# 06_Gyroscope.net
KiCad netlist of a schematic drawn in Altium Designer
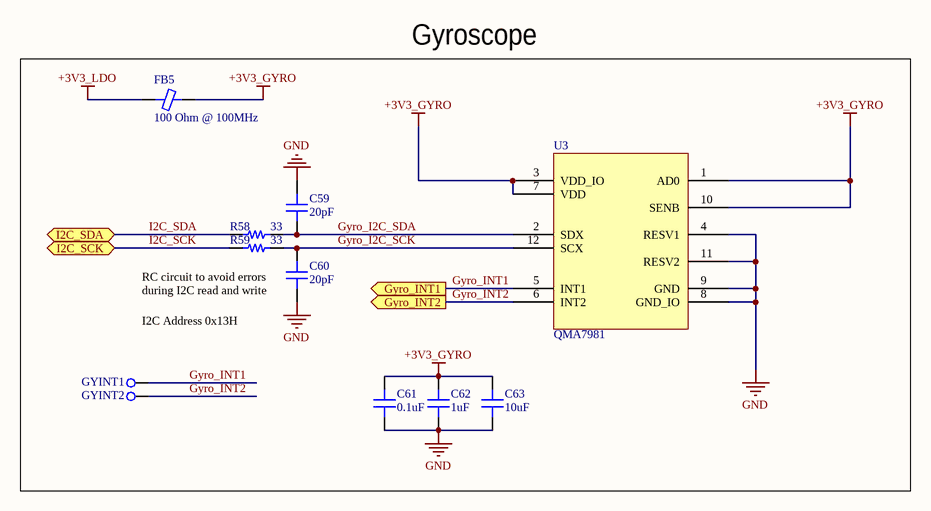
[diagram p0: [06] Gyroscope.SchDoc]

(export (version "E")
  (design (tool "Eeschema 10.0.6"))
  (components
    (comp (ref "C59")
      (value "20pF")
      (footprint "CAP 0402/1005")
      (description "CAP CER 20PF 25V NP0 0402")
      (fields
        (field (name "PART NUMBER") "GRM1555C1E200JA01D")
        (field (name "MANUFACTURER") "Murata Electronics North America")
      )
      (libsource (lib "Celestial Library Database") (part "Capacitor"))
    )
    (comp (ref "C60")
      (value "20pF")
      (footprint "CAP 0402/1005")
      (description "CAP CER 20PF 25V NP0 0402")
      (fields
        (field (name "PART NUMBER") "GRM1555C1E200JA01D")
        (field (name "MANUFACTURER") "Murata Electronics North America")
      )
      (libsource (lib "Celestial Library Database") (part "Capacitor"))
    )
    (comp (ref "C61")
      (value "0.1uF")
      (footprint "CAP 0402/1005")
      (description "CAP CER 0.1UF 10V X7R 0402")
      (fields
        (field (name "PART NUMBER") "C1005X7R1A104K050BB")
        (field (name "MANUFACTURER") "TDK Corporation")
      )
      (libsource (lib "Celestial Library Database") (part "Capacitor"))
    )
    (comp (ref "C62")
      (value "1uF")
      (footprint "CAP 0603/1608")
      (description "CAP CER 1UF 10V X7R 0603")
      (fields
        (field (name "PART NUMBER") "CGB3B1X7R1A105K055AC")
        (field (name "MANUFACTURER") "TDK Corporation")
      )
      (libsource (lib "Celestial Library Database") (part "Capacitor"))
    )
    (comp (ref "C63")
      (value "10uF")
      (footprint "CAP 0603/1608")
      (description "CAP CER 10UF 10V X5R 0603")
      (fields
        (field (name "PART NUMBER") "C1608X5R1A106M080AC")
        (field (name "MANUFACTURER") "TDK Corporation")
      )
      (libsource (lib "Celestial Library Database") (part "Capacitor"))
    )
    (comp (ref "FB5")
      (value "100 Ohm @ 100MHz")
      (footprint "FER 0603/1608")
      (description "FERRITE CHIP 100 OHM 0603")
      (fields (field (name "PART NUMBER") "BKP1608HS101-T") (field (name "MANUFACTURER") "Taiyo Yuden"))
      (libsource (lib "Celestial Library Database") (part "Ferrite Chip"))
    )
    (comp (ref "GYINT1")
      (value "RCT-0C")
      (footprint "3D FootPrint_Backup:0.5mm-TestPad")
      (description "0805 PROBE PAD")
      (fields (field (name "MANUFACTURER") "TE Connectivity AMP Connectors"))
      (libsource (lib "Celestial Library Database") (part "Test Point"))
    )
    (comp (ref "GYINT2")
      (value "RCT-0C")
      (footprint "3D FootPrint_Backup:0.5mm-TestPad")
      (description "0805 PROBE PAD")
      (fields (field (name "MANUFACTURER") "TE Connectivity AMP Connectors"))
      (libsource (lib "Celestial Library Database") (part "Test Point"))
    )
    (comp (ref "R58")
      (value "33")
      (footprint "RES 0402/1005")
      (description "RES SMD 33 OHM 5% 1/10W 0402")
      (fields
        (field (name "PART NUMBER") "ERJ-2GEJ330X")
        (field (name "MANUFACTURER") "Panasonic Electronic Components")
      )
      (libsource (lib "Celestial Library Database") (part "Resistor"))
    )
    (comp (ref "R59")
      (value "33")
      (footprint "RES 0402/1005")
      (description "RES SMD 33 OHM 5% 1/10W 0402")
      (fields
        (field (name "PART NUMBER") "ERJ-2GEJ330X")
        (field (name "MANUFACTURER") "Panasonic Electronic Components")
      )
      (libsource (lib "Celestial Library Database") (part "Resistor"))
    )
    (comp (ref "U3")
      (value "QMA7981")
      (footprint "LGA-12 2x2")
      (description "3 AXIS ACCEL 12LGA")
      (fields (field (name "MANUFACTURER") "QST"))
      (libsource (lib "Celestial Library Database") (part "QMA7981"))
    )
  )
  (nets
    (net (code "1") (name "+3V3_GYRO") (class "Default")
      (node (ref "C61") (pin "2") (pinfunction "2_2") (pintype "passive"))
      (node (ref "C62") (pin "2") (pinfunction "2_2") (pintype "passive"))
      (node (ref "C63") (pin "2") (pinfunction "2_2") (pintype "passive"))
      (node (ref "FB5") (pin "2") (pinfunction "2_2") (pintype "passive"))
      (node (ref "U3") (pin "1") (pinfunction "AD0_1") (pintype "passive"))
      (node (ref "U3") (pin "10") (pinfunction "SENB_10") (pintype "passive"))
      (node (ref "U3") (pin "3") (pinfunction "VDD_IO_3") (pintype "passive"))
      (node (ref "U3") (pin "7") (pinfunction "VDD_7") (pintype "passive"))
    )
    (net (code "2") (name "+3V3_LDO") (class "Default")
      (node (ref "FB5") (pin "1") (pinfunction "1_1") (pintype "passive"))
    )
    (net (code "3") (name "/Gyro_I2C_SCK") (class "Default")
      (node (ref "C60") (pin "2") (pinfunction "2_2") (pintype "passive"))
      (node (ref "R59") (pin "2") (pinfunction "2_2") (pintype "passive"))
      (node (ref "U3") (pin "12") (pinfunction "SCX_12") (pintype "passive"))
    )
    (net (code "4") (name "/Gyro_I2C_SDA") (class "Default")
      (node (ref "C59") (pin "1") (pinfunction "1_1") (pintype "passive"))
      (node (ref "R58") (pin "2") (pinfunction "2_2") (pintype "passive"))
      (node (ref "U3") (pin "2") (pinfunction "SDX_2") (pintype "passive"))
    )
    (net (code "5") (name "/Gyro_INT1") (class "Default")
      (node (ref "GYINT1") (pin "1") (pinfunction "TP_1") (pintype "passive"))
      (node (ref "U3") (pin "5") (pinfunction "INT1_5") (pintype "passive"))
    )
    (net (code "6") (name "/Gyro_INT2") (class "Default")
      (node (ref "GYINT2") (pin "1") (pinfunction "TP_1") (pintype "passive"))
      (node (ref "U3") (pin "6") (pinfunction "INT2_6") (pintype "passive"))
    )
    (net (code "7") (name "/I2C_SCK") (class "Default")
      (node (ref "R59") (pin "1") (pinfunction "1_1") (pintype "passive"))
    )
    (net (code "8") (name "/I2C_SDA") (class "Default")
      (node (ref "R58") (pin "1") (pinfunction "1_1") (pintype "passive"))
    )
    (net (code "9") (name "GND") (class "Default")
      (node (ref "C59") (pin "2") (pinfunction "2_2") (pintype "passive"))
      (node (ref "C60") (pin "1") (pinfunction "1_1") (pintype "passive"))
      (node (ref "C61") (pin "1") (pinfunction "1_1") (pintype "passive"))
      (node (ref "C62") (pin "1") (pinfunction "1_1") (pintype "passive"))
      (node (ref "C63") (pin "1") (pinfunction "1_1") (pintype "passive"))
      (node (ref "U3") (pin "11") (pinfunction "RESV2_11") (pintype "passive"))
      (node (ref "U3") (pin "4") (pinfunction "RESV1_4") (pintype "passive"))
      (node (ref "U3") (pin "8") (pinfunction "GND_IO_8") (pintype "passive"))
      (node (ref "U3") (pin "9") (pinfunction "GND_9") (pintype "passive"))
    )
  )
)
